# PG03_Schematic_Sheet1.net
KiCad netlist of a schematic drawn in Altium Designer
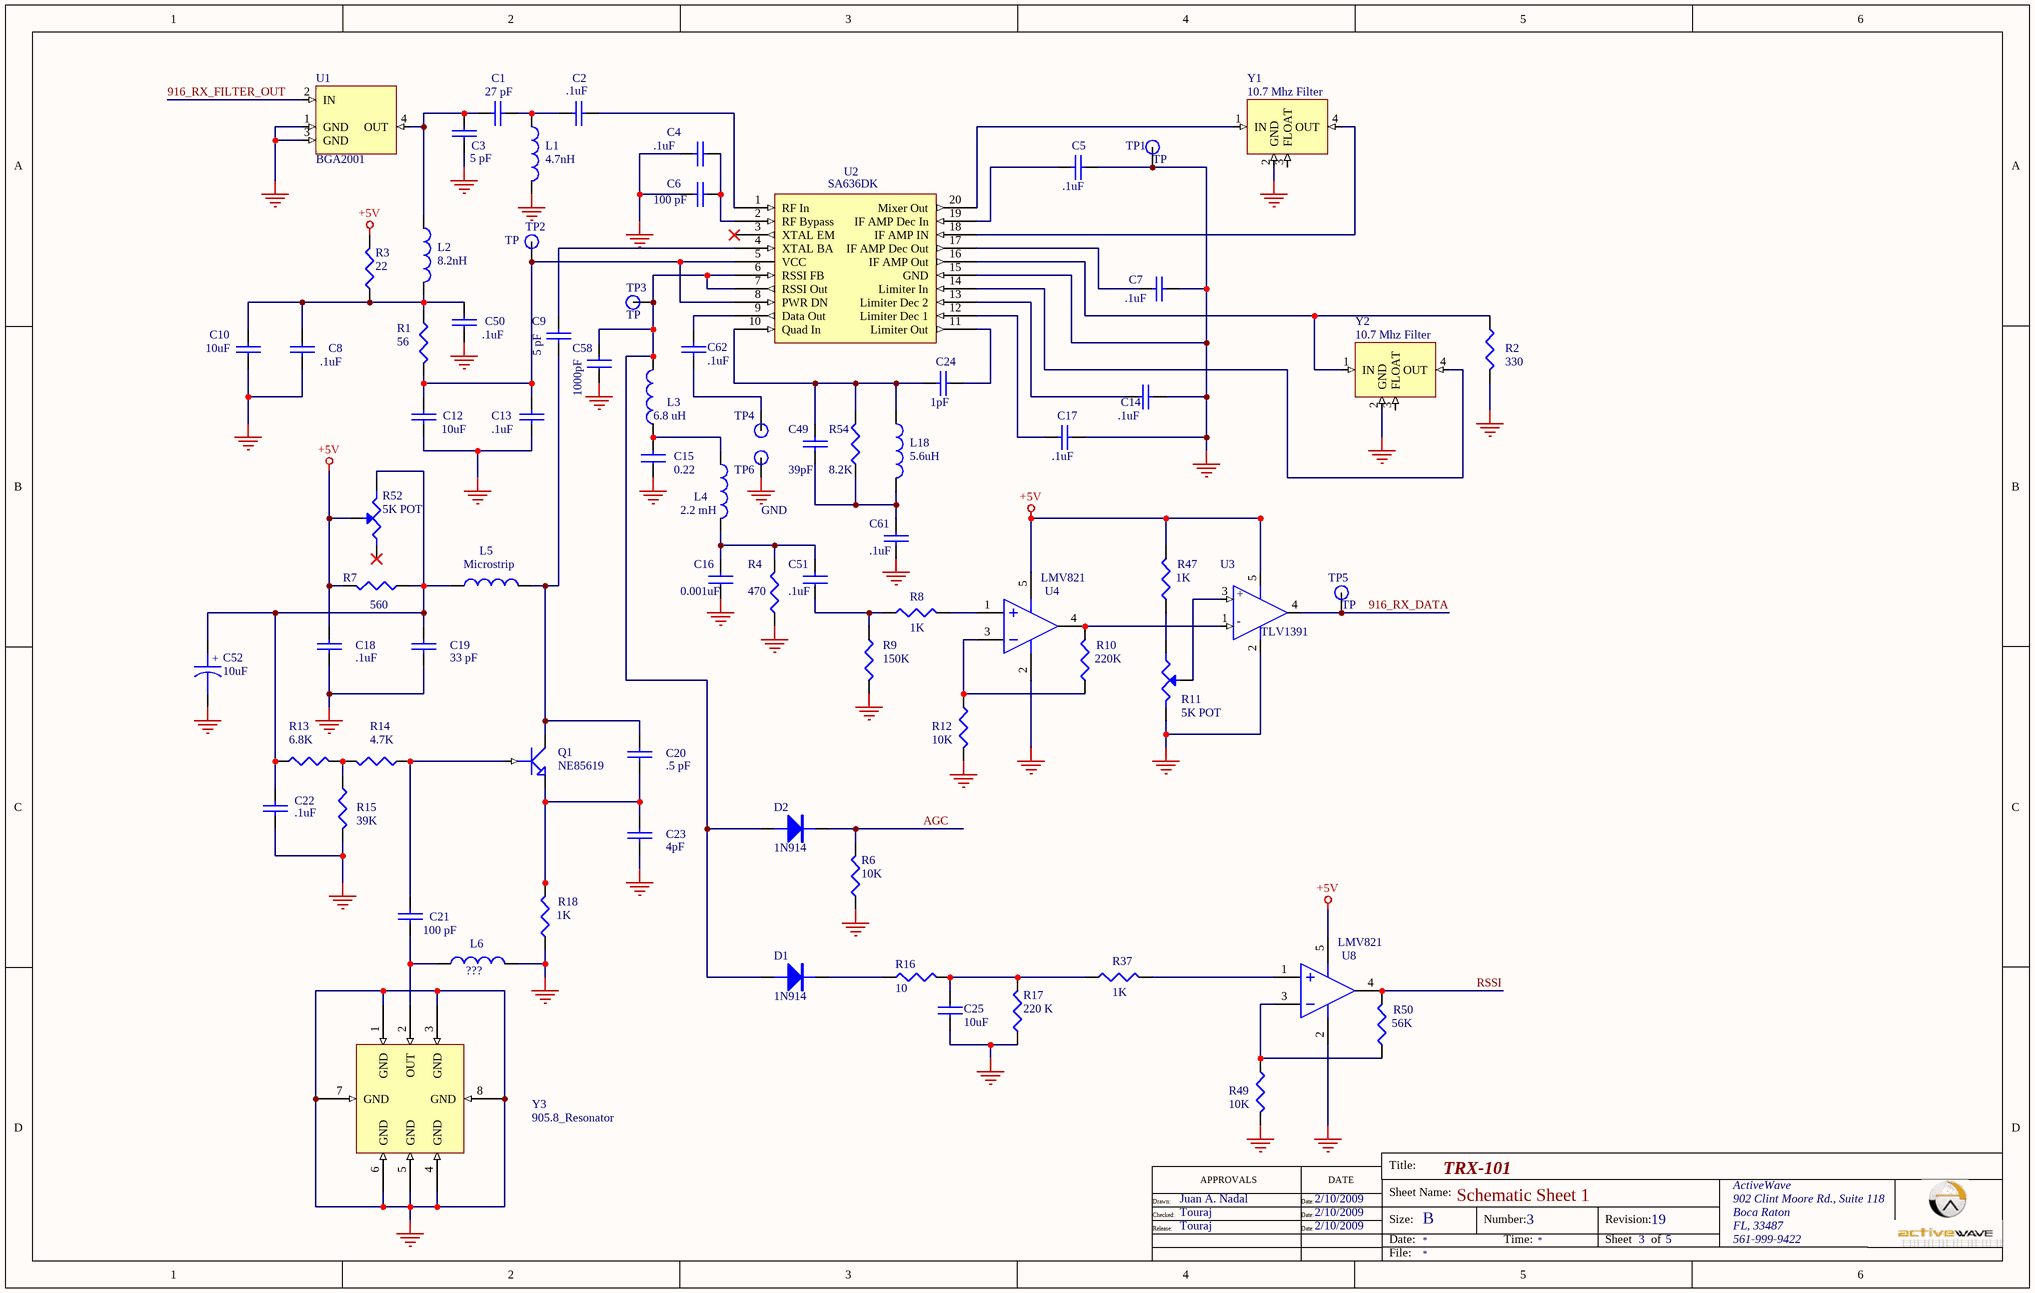
[diagram p0: PG03_Schematic Sheet1.SchDoc]

(export (version "E")
  (design (tool "Eeschema 10.0.6"))
  (components
    (comp (ref "C1")
      (value "27 pF")
      (footprint "0603")
      (description "Capacitor")
      (libsource (lib "*") (part "CAP"))
    )
    (comp (ref "C2")
      (value ".1uF")
      (footprint "0603")
      (description "Capacitor")
      (libsource (lib "*") (part "CAP"))
    )
    (comp (ref "C3")
      (value "5 pF")
      (footprint "0603")
      (description "Capacitor")
      (libsource (lib "*") (part "CAP"))
    )
    (comp (ref "C4")
      (value ".1uF")
      (footprint "0603")
      (description "Capacitor")
      (libsource (lib "*") (part "CAP"))
    )
    (comp (ref "C5")
      (value ".1uF")
      (footprint "0603")
      (description "Capacitor")
      (libsource (lib "*") (part "CAP"))
    )
    (comp (ref "C6")
      (value "100 pF")
      (footprint "0603")
      (description "Capacitor")
      (libsource (lib "*") (part "CAP"))
    )
    (comp (ref "C7")
      (value ".1uF")
      (footprint "0603")
      (description "Capacitor")
      (libsource (lib "*") (part "CAP"))
    )
    (comp (ref "C8")
      (value ".1uF")
      (footprint "0603")
      (description "Capacitor")
      (libsource (lib "*") (part "CAP"))
    )
    (comp (ref "C9")
      (value "5 pF")
      (footprint "0603")
      (description "Capacitor")
      (libsource (lib "*") (part "CAP"))
    )
    (comp (ref "C10")
      (value "10uF")
      (footprint "CAP A CASE")
      (description "Capacitor")
      (libsource (lib "*") (part "CAP"))
    )
    (comp (ref "C12")
      (value "10uF")
      (footprint "CAP A CASE")
      (description "Capacitor")
      (libsource (lib "*") (part "CAP"))
    )
    (comp (ref "C13")
      (value ".1uF")
      (footprint "0603")
      (description "Capacitor")
      (libsource (lib "*") (part "CAP"))
    )
    (comp (ref "C14")
      (value ".1uF")
      (footprint "0603")
      (description "Capacitor")
      (libsource (lib "*") (part "CAP"))
    )
    (comp (ref "C15") (value "0.22") (footprint "0603") (libsource (lib "*") (part "CAP_NP")))
    (comp (ref "C16") (value "0.001uF") (footprint "0603") (libsource (lib "*") (part "CAP_NP")))
    (comp (ref "C17")
      (value ".1uF")
      (footprint "0603")
      (description "Capacitor")
      (libsource (lib "*") (part "CAP"))
    )
    (comp (ref "C18")
      (value ".1uF")
      (footprint "0603")
      (description "Capacitor")
      (libsource (lib "*") (part "CAP"))
    )
    (comp (ref "C19")
      (value "33 pF")
      (footprint "0603")
      (description "Capacitor")
      (libsource (lib "*") (part "CAP"))
    )
    (comp (ref "C20")
      (value ".5 pF")
      (footprint "0603")
      (description "Capacitor")
      (libsource (lib "*") (part "CAP"))
    )
    (comp (ref "C21")
      (value "100 pF")
      (footprint "0603")
      (description "Capacitor")
      (libsource (lib "*") (part "CAP"))
    )
    (comp (ref "C22")
      (value ".1uF")
      (footprint "0603")
      (description "Capacitor")
      (libsource (lib "*") (part "CAP"))
    )
    (comp (ref "C23")
      (value "4pF")
      (footprint "0603")
      (description "Capacitor")
      (libsource (lib "*") (part "CAP"))
    )
    (comp (ref "C24")
      (value "1pF")
      (footprint "0603")
      (description "Capacitor")
      (libsource (lib "*") (part "CAP"))
    )
    (comp (ref "C25") (value "10uF") (footprint "CAP A CASE") (libsource (lib "*") (part "CAP_NP")))
    (comp (ref "C49")
      (value "39pF")
      (footprint "0603")
      (description "Capacitor")
      (libsource (lib "*") (part "CAP"))
    )
    (comp (ref "C50")
      (value ".1uF")
      (footprint "0603")
      (description "Capacitor")
      (libsource (lib "*") (part "CAP"))
    )
    (comp (ref "C51") (value ".1uF") (footprint "0603") (libsource (lib "*") (part "CAP_NP")))
    (comp (ref "C52")
      (value "10uF")
      (footprint "CAP A CASE")
      (description "Capacitor")
      (libsource (lib "*") (part "CAPACITOR POL"))
    )
    (comp (ref "C58") (value "1000pF") (footprint "0603") (libsource (lib "*") (part "CAP_NP")))
    (comp (ref "C61")
      (value ".1uF")
      (footprint "0603")
      (description "Capacitor")
      (libsource (lib "*") (part "CAP"))
    )
    (comp (ref "C62")
      (value ".1uF")
      (footprint "0603")
      (description "Capacitor")
      (libsource (lib "*") (part "CAP"))
    )
    (comp (ref "D1")
      (value "1N914")
      (footprint "SOT23 DIODE")
      (description "Diode")
      (libsource (lib "*") (part "DIODE"))
    )
    (comp (ref "D2")
      (value "1N914")
      (footprint "SOT23 DIODE")
      (description "Diode")
      (libsource (lib "*") (part "DIODE"))
    )
    (comp (ref "L1") (value "4.7nH") (footprint "0603") (libsource (lib "*") (part "INDUCTOR")))
    (comp (ref "L2") (value "8.2nH") (footprint "0603") (libsource (lib "*") (part "INDUCTOR")))
    (comp (ref "L3") (value "6.8 uH") (footprint "0805") (libsource (lib "*") (part "INDUCTOR")))
    (comp (ref "L4") (value "2.2 mH") (footprint "COIL TKS5540CT-ND") (libsource (lib "*") (part "INDUCTOR")))
    (comp (ref "L5") (value "Microstrip") (footprint "MICROSTRIP") (libsource (lib "*") (part "INDUCTOR")))
    (comp (ref "L6") (value "???") (footprint "0603") (libsource (lib "*") (part "INDUCTOR")))
    (comp (ref "L18") (value "5.6uH") (footprint "0603") (libsource (lib "*") (part "INDUCTOR")))
    (comp (ref "Q1")
      (value "NE85619")
      (footprint "3 PIN ULTRA SUPER MINI MOLD")
      (description "NPN Transistor")
      (libsource (lib "*") (part "NPN1"))
    )
    (comp (ref "R1") (value "56") (footprint "0603") (libsource (lib "*") (part "R")))
    (comp (ref "R2") (value "330") (footprint "0603") (libsource (lib "*") (part "R")))
    (comp (ref "R3") (value "22") (footprint "0603") (libsource (lib "*") (part "R")))
    (comp (ref "R4") (value "470") (footprint "0603") (libsource (lib "*") (part "R")))
    (comp (ref "R6") (value "10K") (footprint "0603") (libsource (lib "*") (part "R")))
    (comp (ref "R7") (value "560") (footprint "0603") (libsource (lib "*") (part "RESISTOR")))
    (comp (ref "R8") (value "1K") (footprint "0603") (libsource (lib "*") (part "R")))
    (comp (ref "R9") (value "150K") (footprint "0603") (libsource (lib "*") (part "R")))
    (comp (ref "R10") (value "220K") (footprint "0603") (libsource (lib "*") (part "R")))
    (comp (ref "R11")
      (value "5K POT")
      (footprint "POT PANA EVN5")
      (description "Potentiometer")
      (libsource (lib "*") (part "POT1"))
    )
    (comp (ref "R12") (value "10K") (footprint "0603") (libsource (lib "*") (part "R")))
    (comp (ref "R13") (value "6.8K") (footprint "0603") (libsource (lib "*") (part "RESISTOR")))
    (comp (ref "R14") (value "4.7K") (footprint "0603") (libsource (lib "*") (part "RESISTOR")))
    (comp (ref "R15") (value "39K") (footprint "0603") (libsource (lib "*") (part "RESISTOR")))
    (comp (ref "R16") (value "10") (footprint "0603") (libsource (lib "*") (part "R")))
    (comp (ref "R17") (value "220 K") (footprint "0603") (libsource (lib "*") (part "R")))
    (comp (ref "R18") (value "1K") (footprint "0603") (libsource (lib "*") (part "RESISTOR")))
    (comp (ref "R37") (value "1K") (footprint "0603") (libsource (lib "*") (part "R")))
    (comp (ref "R47") (value "1K") (footprint "0603") (libsource (lib "*") (part "R")))
    (comp (ref "R49") (value "10K") (footprint "0603") (libsource (lib "*") (part "R")))
    (comp (ref "R50") (value "56K") (footprint "0603") (libsource (lib "*") (part "R")))
    (comp (ref "R52")
      (value "5K POT")
      (footprint "POT PANA EVN5")
      (description "Potentiometer")
      (libsource (lib "") (part "POT1_1"))
    )
    (comp (ref "R54") (value "8.2K") (footprint "0603") (libsource (lib "*") (part "R")))
    (comp (ref "TP1") (value "TP") (footprint "TESTPOINT") (libsource (lib "TRX-101R16") (part "TP")))
    (comp (ref "TP2") (value "TP") (footprint "TESTPOINT") (libsource (lib "TRX-101R16") (part "TP")))
    (comp (ref "TP3") (value "TP") (footprint "TESTPOINT") (libsource (lib "TRX-101R16") (part "TP")))
    (comp (ref "TP4") (value "TP") (footprint "TESTPOINT") (libsource (lib "TRX-101R16") (part "TP")))
    (comp (ref "TP5") (value "TP") (footprint "TESTPOINT") (libsource (lib "TRX-101R16") (part "TP")))
    (comp (ref "TP6") (value "GND") (footprint "TESTPOINT") (libsource (lib "TRX-101R16") (part "TP")))
    (comp (ref "U1") (value "BGA2001") (footprint "SOT343") (libsource (lib "*") (part "BGA2001")))
    (comp (ref "U2") (value "SA636DK") (footprint "SSOP20") (libsource (lib "*") (part "SA636DK")))
    (comp (ref "U3") (value "TLV1391") (footprint "SOT25") (libsource (lib "*") (part "TLV1391")))
    (comp (ref "U4") (value "LMV821") (footprint "SOT25") (libsource (lib "*") (part "OPAMP1")))
    (comp (ref "U8") (value "LMV821") (footprint "SOT25") (libsource (lib "*") (part "OPAMP1")))
    (comp (ref "Y1") (value "10.7 Mhz Filter") (footprint "FILTER2") (libsource (lib "*") (part "FILTER2")))
    (comp (ref "Y2") (value "10.7 Mhz Filter") (footprint "FILTER2") (libsource (lib "*") (part "FILTER2")))
    (comp (ref "Y3")
      (value "905.8_Resonator")
      (footprint "RESONATOR")
      (libsource (lib "TRX-101_16") (part "RESONATOR2"))
    )
  )
  (nets
    (net (code "1") (name "+5V") (class "Default")
      (node (ref "C18") (pin "1") (pinfunction "1_1") (pintype "passive"))
      (node (ref "R3") (pin "2") (pinfunction "2_2") (pintype "passive"))
      (node (ref "R47") (pin "2") (pinfunction "2_2") (pintype "passive"))
      (node (ref "R52") (pin "2") (pinfunction "2_2") (pintype "passive"))
      (node (ref "R7") (pin "2") (pinfunction "2_2") (pintype "passive"))
      (node (ref "U3") (pin "5") (pinfunction "VDD_5") (pintype "power_in"))
      (node (ref "U4") (pin "5") (pinfunction "5_5") (pintype "passive"))
      (node (ref "U8") (pin "5") (pinfunction "5_5") (pintype "passive"))
    )
    (net (code "2") (name "/916_RX_DATA") (class "Default")
      (node (ref "TP5") (pin "1") (pinfunction "TP_1") (pintype "passive"))
      (node (ref "U3") (pin "4") (pinfunction "OUT_4") (pintype "open_collector"))
    )
    (net (code "3") (name "/916_RX_FILTER_OUT") (class "Default")
      (node (ref "U1") (pin "2") (pinfunction "IN_2") (pintype "input"))
    )
    (net (code "4") (name "/AGC") (class "Default")
      (node (ref "D2") (pin "K") (pinfunction "K_K") (pintype "passive"))
      (node (ref "R6") (pin "1") (pinfunction "1_1") (pintype "passive"))
    )
    (net (code "5") (name "/RSSI") (class "Default")
      (node (ref "R50") (pin "2") (pinfunction "2_2") (pintype "passive"))
      (node (ref "U8") (pin "4") (pinfunction "4_4") (pintype "passive"))
    )
    (net (code "6") (name "GND_SIGNAL") (class "Default")
      (node (ref "C10") (pin "2") (pinfunction "2_2") (pintype "passive"))
      (node (ref "C12") (pin "2") (pinfunction "2_2") (pintype "passive"))
      (node (ref "C13") (pin "2") (pinfunction "2_2") (pintype "passive"))
      (node (ref "C14") (pin "2") (pinfunction "2_2") (pintype "passive"))
      (node (ref "C15") (pin "1") (pinfunction "1_1") (pintype "passive"))
      (node (ref "C16") (pin "1") (pinfunction "1_1") (pintype "passive"))
      (node (ref "C17") (pin "2") (pinfunction "2_2") (pintype "passive"))
      (node (ref "C18") (pin "2") (pinfunction "2_2") (pintype "passive"))
      (node (ref "C19") (pin "2") (pinfunction "2_2") (pintype "passive"))
      (node (ref "C22") (pin "2") (pinfunction "2_2") (pintype "passive"))
      (node (ref "C23") (pin "2") (pinfunction "2_2") (pintype "passive"))
      (node (ref "C25") (pin "2") (pinfunction "2_2") (pintype "passive"))
      (node (ref "C3") (pin "2") (pinfunction "2_2") (pintype "passive"))
      (node (ref "C4") (pin "1") (pinfunction "1_1") (pintype "passive"))
      (node (ref "C5") (pin "2") (pinfunction "2_2") (pintype "passive"))
      (node (ref "C50") (pin "2") (pinfunction "2_2") (pintype "passive"))
      (node (ref "C52") (pin "2") (pinfunction "2_2") (pintype "passive"))
      (node (ref "C58") (pin "1") (pinfunction "1_1") (pintype "passive"))
      (node (ref "C6") (pin "1") (pinfunction "1_1") (pintype "passive"))
      (node (ref "C61") (pin "2") (pinfunction "2_2") (pintype "passive"))
      (node (ref "C7") (pin "2") (pinfunction "2_2") (pintype "passive"))
      (node (ref "C8") (pin "2") (pinfunction "2_2") (pintype "passive"))
      (node (ref "L1") (pin "2") (pinfunction "2_2") (pintype "passive"))
      (node (ref "L6") (pin "2") (pinfunction "2_2") (pintype "passive"))
      (node (ref "R11") (pin "3") (pinfunction "3_3") (pintype "passive"))
      (node (ref "R12") (pin "2") (pinfunction "2_2") (pintype "passive"))
      (node (ref "R15") (pin "2") (pinfunction "2_2") (pintype "passive"))
      (node (ref "R17") (pin "2") (pinfunction "2_2") (pintype "passive"))
      (node (ref "R18") (pin "1") (pinfunction "1_1") (pintype "passive"))
      (node (ref "R2") (pin "2") (pinfunction "2_2") (pintype "passive"))
      (node (ref "R4") (pin "1") (pinfunction "1_1") (pintype "passive"))
      (node (ref "R49") (pin "2") (pinfunction "2_2") (pintype "passive"))
      (node (ref "R6") (pin "2") (pinfunction "2_2") (pintype "passive"))
      (node (ref "R9") (pin "2") (pinfunction "2_2") (pintype "passive"))
      (node (ref "TP1") (pin "1") (pinfunction "TP_1") (pintype "passive"))
      (node (ref "TP6") (pin "1") (pinfunction "TP_1") (pintype "passive"))
      (node (ref "U1") (pin "1") (pinfunction "GND_1") (pintype "input"))
      (node (ref "U1") (pin "3") (pinfunction "GND_3") (pintype "input"))
      (node (ref "U2") (pin "15") (pinfunction "GND_15") (pintype "input"))
      (node (ref "U3") (pin "2") (pinfunction "VSS_2") (pintype "power_in"))
      (node (ref "U4") (pin "2") (pinfunction "2_2") (pintype "passive"))
      (node (ref "U8") (pin "2") (pinfunction "2_2") (pintype "passive"))
      (node (ref "Y1") (pin "2") (pinfunction "GND_2") (pintype "input"))
      (node (ref "Y2") (pin "2") (pinfunction "GND_2") (pintype "input"))
      (node (ref "Y3") (pin "1") (pinfunction "GND_1") (pintype "input"))
      (node (ref "Y3") (pin "3") (pinfunction "GND_3") (pintype "input"))
      (node (ref "Y3") (pin "4") (pinfunction "GND_4") (pintype "input"))
      (node (ref "Y3") (pin "5") (pinfunction "GND_5") (pintype "input"))
      (node (ref "Y3") (pin "6") (pinfunction "GND_6") (pintype "input"))
      (node (ref "Y3") (pin "7") (pinfunction "GND_7") (pintype "input"))
      (node (ref "Y3") (pin "8") (pinfunction "GND_8") (pintype "input"))
    )
    (net (code "7") (name "Net-(C1-Pad2)") (class "Default")
      (node (ref "C1") (pin "2") (pinfunction "2_2") (pintype "passive"))
      (node (ref "C2") (pin "1") (pinfunction "1_1") (pintype "passive"))
      (node (ref "L1") (pin "1") (pinfunction "1_1") (pintype "passive"))
    )
    (net (code "8") (name "Net-(C10-Pad1)") (class "Default")
      (node (ref "C10") (pin "1") (pinfunction "1_1") (pintype "passive"))
      (node (ref "C50") (pin "1") (pinfunction "1_1") (pintype "passive"))
      (node (ref "C8") (pin "1") (pinfunction "1_1") (pintype "passive"))
      (node (ref "L2") (pin "2") (pinfunction "2_2") (pintype "passive"))
      (node (ref "R1") (pin "1") (pinfunction "1_1") (pintype "passive"))
      (node (ref "R3") (pin "1") (pinfunction "1_1") (pintype "passive"))
    )
    (net (code "9") (name "Net-(C15-Pad2)") (class "Default")
      (node (ref "C15") (pin "2") (pinfunction "2_2") (pintype "passive"))
      (node (ref "L3") (pin "1") (pinfunction "1_1") (pintype "passive"))
      (node (ref "L4") (pin "1") (pinfunction "1_1") (pintype "passive"))
    )
    (net (code "10") (name "Net-(C16-Pad2)") (class "Default")
      (node (ref "C16") (pin "2") (pinfunction "2_2") (pintype "passive"))
      (node (ref "C51") (pin "2") (pinfunction "2_2") (pintype "passive"))
      (node (ref "L4") (pin "2") (pinfunction "2_2") (pintype "passive"))
      (node (ref "R4") (pin "2") (pinfunction "2_2") (pintype "passive"))
    )
    (net (code "11") (name "Net-(C19-Pad1)") (class "Default")
      (node (ref "C19") (pin "1") (pinfunction "1_1") (pintype "passive"))
      (node (ref "C22") (pin "1") (pinfunction "1_1") (pintype "passive"))
      (node (ref "C52") (pin "1") (pinfunction "1_1") (pintype "passive"))
      (node (ref "L5") (pin "1") (pinfunction "1_1") (pintype "passive"))
      (node (ref "R13") (pin "1") (pinfunction "1_1") (pintype "passive"))
      (node (ref "R52") (pin "1") (pinfunction "1_1") (pintype "passive"))
      (node (ref "R7") (pin "1") (pinfunction "1_1") (pintype "passive"))
    )
    (net (code "12") (name "Net-(C20-Pad1)") (class "Default")
      (node (ref "C20") (pin "1") (pinfunction "1_1") (pintype "passive"))
      (node (ref "C9") (pin "1") (pinfunction "1_1") (pintype "passive"))
      (node (ref "L5") (pin "2") (pinfunction "2_2") (pintype "passive"))
      (node (ref "Q1") (pin "C") (pinfunction "C_C") (pintype "passive"))
    )
    (net (code "13") (name "Net-(C20-Pad2)") (class "Default")
      (node (ref "C20") (pin "2") (pinfunction "2_2") (pintype "passive"))
      (node (ref "C23") (pin "1") (pinfunction "1_1") (pintype "passive"))
      (node (ref "Q1") (pin "E") (pinfunction "E_E") (pintype "passive"))
      (node (ref "R18") (pin "2") (pinfunction "2_2") (pintype "passive"))
    )
    (net (code "14") (name "Net-(C21-Pad1)") (class "Default")
      (node (ref "C21") (pin "1") (pinfunction "1_1") (pintype "passive"))
      (node (ref "Q1") (pin "B") (pinfunction "B_B") (pintype "input"))
      (node (ref "R14") (pin "1") (pinfunction "1_1") (pintype "passive"))
    )
    (net (code "15") (name "Net-(C25-Pad1)") (class "Default")
      (node (ref "C25") (pin "1") (pinfunction "1_1") (pintype "passive"))
      (node (ref "R16") (pin "1") (pinfunction "1_1") (pintype "passive"))
      (node (ref "R17") (pin "1") (pinfunction "1_1") (pintype "passive"))
      (node (ref "R37") (pin "1") (pinfunction "1_1") (pintype "passive"))
    )
    (net (code "16") (name "Net-(C49-Pad2)") (class "Default")
      (node (ref "C49") (pin "2") (pinfunction "2_2") (pintype "passive"))
      (node (ref "C61") (pin "1") (pinfunction "1_1") (pintype "passive"))
      (node (ref "L18") (pin "2") (pinfunction "2_2") (pintype "passive"))
      (node (ref "R54") (pin "1") (pinfunction "1_1") (pintype "passive"))
    )
    (net (code "17") (name "Net-(C51-Pad1)") (class "Default")
      (node (ref "C51") (pin "1") (pinfunction "1_1") (pintype "passive"))
      (node (ref "R8") (pin "1") (pinfunction "1_1") (pintype "passive"))
      (node (ref "R9") (pin "1") (pinfunction "1_1") (pintype "passive"))
    )
    (net (code "18") (name "Net-(D1-PadK)") (class "Default")
      (node (ref "D1") (pin "K") (pinfunction "K_K") (pintype "passive"))
      (node (ref "R16") (pin "2") (pinfunction "2_2") (pintype "passive"))
    )
    (net (code "19") (name "Net-(R8-Pad2)") (class "Default")
      (node (ref "R8") (pin "2") (pinfunction "2_2") (pintype "passive"))
      (node (ref "U4") (pin "1") (pinfunction "1_1") (pintype "passive"))
    )
    (net (code "20") (name "Net-(R10-Pad1)") (class "Default")
      (node (ref "R10") (pin "1") (pinfunction "1_1") (pintype "passive"))
      (node (ref "R12") (pin "1") (pinfunction "1_1") (pintype "passive"))
      (node (ref "U4") (pin "3") (pinfunction "3_3") (pintype "passive"))
    )
    (net (code "21") (name "Net-(R11-Pad1)") (class "Default")
      (node (ref "R11") (pin "1") (pinfunction "1_1") (pintype "passive"))
      (node (ref "R47") (pin "1") (pinfunction "1_1") (pintype "passive"))
    )
    (net (code "22") (name "Net-(R13-Pad2)") (class "Default")
      (node (ref "R13") (pin "2") (pinfunction "2_2") (pintype "passive"))
      (node (ref "R14") (pin "2") (pinfunction "2_2") (pintype "passive"))
      (node (ref "R15") (pin "1") (pinfunction "1_1") (pintype "passive"))
    )
    (net (code "23") (name "Net-(R37-Pad2)") (class "Default")
      (node (ref "R37") (pin "2") (pinfunction "2_2") (pintype "passive"))
      (node (ref "U8") (pin "1") (pinfunction "1_1") (pintype "passive"))
    )
    (net (code "24") (name "Net-(R49-Pad1)") (class "Default")
      (node (ref "R49") (pin "1") (pinfunction "1_1") (pintype "passive"))
      (node (ref "R50") (pin "1") (pinfunction "1_1") (pintype "passive"))
      (node (ref "U8") (pin "3") (pinfunction "3_3") (pintype "passive"))
    )
    (net (code "25") (name "Net-(TP2-TP)") (class "Default")
      (node (ref "C12") (pin "1") (pinfunction "1_1") (pintype "passive"))
      (node (ref "C13") (pin "1") (pinfunction "1_1") (pintype "passive"))
      (node (ref "R1") (pin "2") (pinfunction "2_2") (pintype "passive"))
      (node (ref "TP2") (pin "1") (pinfunction "TP_1") (pintype "passive"))
      (node (ref "U2") (pin "5") (pinfunction "VCC_5") (pintype "power_in"))
      (node (ref "U2") (pin "8") (pinfunction "PWR_DN_8") (pintype "input"))
    )
    (net (code "26") (name "Net-(TP3-TP)") (class "Default")
      (node (ref "C58") (pin "2") (pinfunction "2_2") (pintype "passive"))
      (node (ref "D1") (pin "A") (pinfunction "A_A") (pintype "passive"))
      (node (ref "D2") (pin "A") (pinfunction "A_A") (pintype "passive"))
      (node (ref "L3") (pin "2") (pinfunction "2_2") (pintype "passive"))
      (node (ref "TP3") (pin "1") (pinfunction "TP_1") (pintype "passive"))
      (node (ref "U2") (pin "6") (pinfunction "RSSI_FB_6") (pintype "input"))
      (node (ref "U2") (pin "7") (pinfunction "RSSI_Out_7") (pintype "output"))
    )
    (net (code "27") (name "Net-(TP4-TP)") (class "Default")
      (node (ref "C62") (pin "1") (pinfunction "1_1") (pintype "passive"))
      (node (ref "TP4") (pin "1") (pinfunction "TP_1") (pintype "passive"))
    )
    (net (code "28") (name "Net-(U1-OUT)") (class "Default")
      (node (ref "C1") (pin "1") (pinfunction "1_1") (pintype "passive"))
      (node (ref "C3") (pin "1") (pinfunction "1_1") (pintype "passive"))
      (node (ref "L2") (pin "1") (pinfunction "1_1") (pintype "passive"))
      (node (ref "U1") (pin "4") (pinfunction "OUT_4") (pintype "input"))
    )
    (net (code "29") (name "Net-(U2-Data_Out)") (class "Default")
      (node (ref "C62") (pin "2") (pinfunction "2_2") (pintype "passive"))
      (node (ref "U2") (pin "9") (pinfunction "Data_Out_9") (pintype "output"))
    )
    (net (code "30") (name "Net-(U2-IF_AMP_Dec_In)") (class "Default")
      (node (ref "C5") (pin "1") (pinfunction "1_1") (pintype "passive"))
      (node (ref "U2") (pin "19") (pinfunction "IF_AMP_Dec_In_19") (pintype "input"))
    )
    (net (code "31") (name "Net-(U2-IF_AMP_Dec_Out)") (class "Default")
      (node (ref "C7") (pin "1") (pinfunction "1_1") (pintype "passive"))
      (node (ref "U2") (pin "17") (pinfunction "IF_AMP_Dec_Out_17") (pintype "output"))
    )
    (net (code "32") (name "Net-(U2-IF_AMP_IN)") (class "Default")
      (node (ref "U2") (pin "18") (pinfunction "IF_AMP_IN_18") (pintype "input"))
      (node (ref "Y1") (pin "4") (pinfunction "OUT_4") (pintype "input"))
    )
    (net (code "33") (name "Net-(U2-IF_AMP_Out)") (class "Default")
      (node (ref "R2") (pin "1") (pinfunction "1_1") (pintype "passive"))
      (node (ref "U2") (pin "16") (pinfunction "IF_AMP_Out_16") (pintype "output"))
      (node (ref "Y2") (pin "1") (pinfunction "IN_1") (pintype "input"))
    )
    (net (code "34") (name "Net-(U2-Limiter_Dec_1)") (class "Default")
      (node (ref "C17") (pin "1") (pinfunction "1_1") (pintype "passive"))
      (node (ref "U2") (pin "12") (pinfunction "Limiter_Dec_1_12") (pintype "input"))
    )
    (net (code "35") (name "Net-(U2-Limiter_Dec_2)") (class "Default")
      (node (ref "C14") (pin "1") (pinfunction "1_1") (pintype "passive"))
      (node (ref "U2") (pin "13") (pinfunction "Limiter_Dec_2_13") (pintype "input"))
    )
    (net (code "36") (name "Net-(U2-Limiter_In)") (class "Default")
      (node (ref "U2") (pin "14") (pinfunction "Limiter_In_14") (pintype "input"))
      (node (ref "Y2") (pin "4") (pinfunction "OUT_4") (pintype "input"))
    )
    (net (code "37") (name "Net-(U2-Limiter_Out)") (class "Default")
      (node (ref "C24") (pin "2") (pinfunction "2_2") (pintype "passive"))
      (node (ref "U2") (pin "11") (pinfunction "Limiter_Out_11") (pintype "output"))
    )
    (net (code "38") (name "Net-(U2-Mixer_Out)") (class "Default")
      (node (ref "U2") (pin "20") (pinfunction "Mixer_Out_20") (pintype "output"))
      (node (ref "Y1") (pin "1") (pinfunction "IN_1") (pintype "input"))
    )
    (net (code "39") (name "Net-(U2-Quad_In)") (class "Default")
      (node (ref "C24") (pin "1") (pinfunction "1_1") (pintype "passive"))
      (node (ref "C49") (pin "1") (pinfunction "1_1") (pintype "passive"))
      (node (ref "L18") (pin "1") (pinfunction "1_1") (pintype "passive"))
      (node (ref "R54") (pin "2") (pinfunction "2_2") (pintype "passive"))
      (node (ref "U2") (pin "10") (pinfunction "Quad_In_10") (pintype "input"))
    )
    (net (code "40") (name "Net-(U2-RF_Bypass)") (class "Default")
      (node (ref "C4") (pin "2") (pinfunction "2_2") (pintype "passive"))
      (node (ref "C6") (pin "2") (pinfunction "2_2") (pintype "passive"))
      (node (ref "U2") (pin "2") (pinfunction "RF_Bypass_2") (pintype "input"))
    )
    (net (code "41") (name "Net-(U2-RF_In)") (class "Default")
      (node (ref "C2") (pin "2") (pinfunction "2_2") (pintype "passive"))
      (node (ref "U2") (pin "1") (pinfunction "RF_In_1") (pintype "input"))
    )
    (net (code "42") (name "Net-(U2-XTAL_BA)") (class "Default")
      (node (ref "C9") (pin "2") (pinfunction "2_2") (pintype "passive"))
      (node (ref "U2") (pin "4") (pinfunction "XTAL_BA_4") (pintype "input"))
    )
    (net (code "43") (name "Net-(U3-+)") (class "Default")
      (node (ref "R11") (pin "2") (pinfunction "2_2") (pintype "passive"))
      (node (ref "U3") (pin "3") (pinfunction "+_3") (pintype "input"))
    )
    (net (code "44") (name "Net-(U3--)") (class "Default")
      (node (ref "R10") (pin "2") (pinfunction "2_2") (pintype "passive"))
      (node (ref "U3") (pin "1") (pinfunction "-_1") (pintype "input"))
      (node (ref "U4") (pin "4") (pinfunction "4_4") (pintype "passive"))
    )
    (net (code "45") (name "Net-(Y3-OUT)") (class "Default")
      (node (ref "C21") (pin "2") (pinfunction "2_2") (pintype "passive"))
      (node (ref "L6") (pin "1") (pinfunction "1_1") (pintype "passive"))
      (node (ref "Y3") (pin "2") (pinfunction "OUT_2") (pintype "input"))
    )
    (net (code "46") (name "unconnected-(R52-Pad3)") (class "Default")
      (node (ref "R52") (pin "3") (pinfunction "3_3") (pintype "passive+no_connect"))
    )
    (net (code "47") (name "unconnected-(U2-XTAL_EM-Pad3)") (class "Default")
      (node (ref "U2") (pin "3") (pinfunction "XTAL_EM_3") (pintype "output+no_connect"))
    )
    (net (code "48") (name "unconnected-(Y1-FLOAT-Pad3)") (class "Default")
      (node (ref "Y1") (pin "3") (pinfunction "FLOAT_3") (pintype "input"))
    )
    (net (code "49") (name "unconnected-(Y2-FLOAT-Pad3)") (class "Default")
      (node (ref "Y2") (pin "3") (pinfunction "FLOAT_3") (pintype "input"))
    )
  )
)
